# open-ebike-latch.net
KiCad netlist of a schematic drawn in EasyEDA
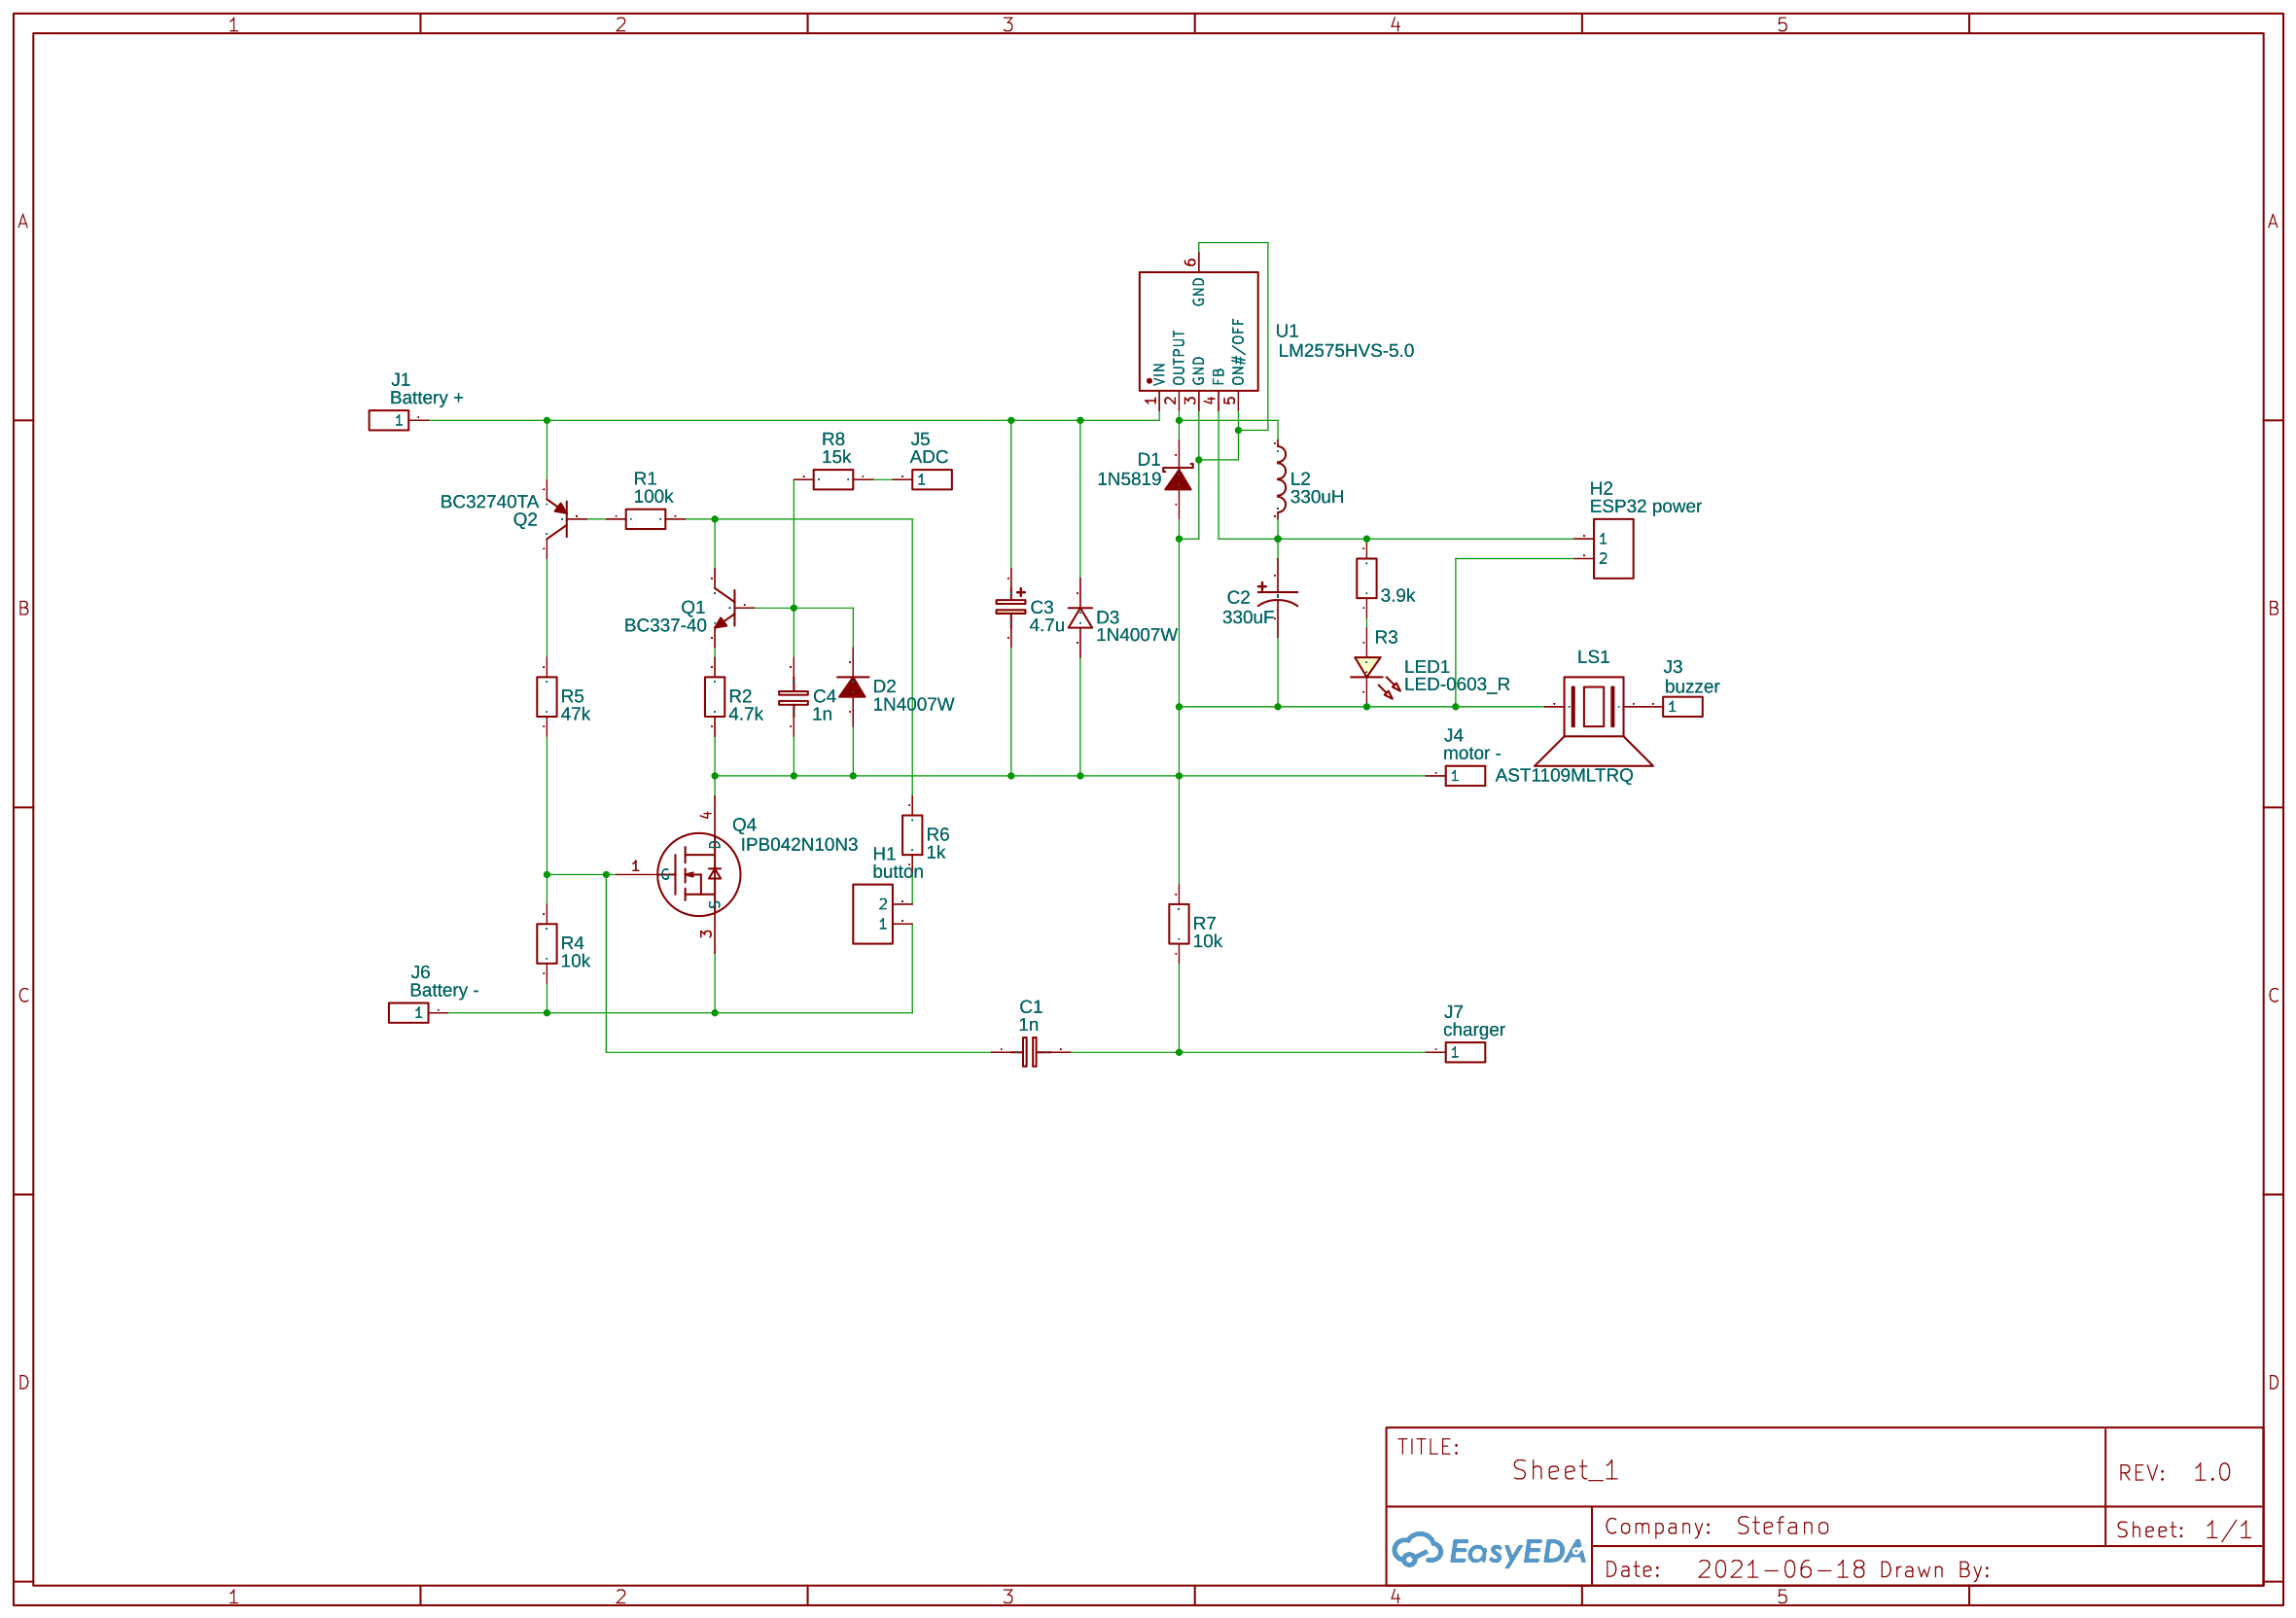
[diagram p0: schematic sheet]

(export (version "E")
  (design (tool "Eeschema 10.0.6"))
  (components
    (comp (ref "C1") (value "1n") (libsource (lib "") (part "C_RAD-0.2_EU_1")))
    (comp (ref "C2")
      (value "330uF")
      (fields
        (field (name "BOM_Manufacturer Part") "UWX0J331MCL1GB")
        (field (name "BOM_Supplier Part") "C445051")
      )
      (libsource (lib "") (part "UWX0J331MCL1GB"))
    )
    (comp (ref "C3") (value "4.7u") (libsource (lib "") (part "CE_TH_D5.0×F2.0_EU")))
    (comp (ref "C4") (value "1n") (libsource (lib "") (part "C_RAD-0.2_EU")))
    (comp (ref "D1")
      (value "1N5819")
      (fields (field (name "BOM_Supplier Part") "C110032"))
      (libsource (lib "") (part "1N5819"))
    )
    (comp (ref "D2")
      (value "1N4007W")
      (fields (field (name "BOM_Supplier Part") "C14516"))
      (libsource (lib "") (part "1N4148"))
    )
    (comp (ref "D3")
      (value "1N4007W")
      (fields (field (name "BOM_Supplier Part") "C328592"))
      (libsource (lib "") (part "1N4007W"))
    )
    (comp (ref "H1")
      (value "button")
      (fields (field (name "BOM_Supplier Part") "C49661"))
      (libsource (lib "") (part "HDR-F-2.54_1x2"))
    )
    (comp (ref "H2")
      (value "ESP32 power")
      (fields (field (name "BOM_Supplier Part") "C49661"))
      (libsource (lib "") (part "HDR-F-2.54_1x2_1"))
    )
    (comp (ref "J1")
      (value "Battery +")
      (fields (field (name "BOM_Supplier Part") "C81276"))
      (libsource (lib "") (part "HDR-M-2.54_1x1_1"))
    )
    (comp (ref "J3")
      (value "buzzer")
      (fields (field (name "BOM_Supplier Part") "C81276"))
      (libsource (lib "") (part "HDR-M-2.54_1x1"))
    )
    (comp (ref "J4")
      (value "motor -")
      (fields (field (name "BOM_Supplier Part") "C81276"))
      (libsource (lib "") (part "HDR-M-2.54_1x1"))
    )
    (comp (ref "J5")
      (value "ADC")
      (fields (field (name "BOM_Supplier Part") "C81276"))
      (libsource (lib "") (part "HDR-M-2.54_1x1"))
    )
    (comp (ref "J6")
      (value "Battery -")
      (fields (field (name "BOM_Supplier Part") "C81276"))
      (libsource (lib "") (part "HDR-M-2.54_1x1_1"))
    )
    (comp (ref "J7")
      (value "charger")
      (fields (field (name "BOM_Supplier Part") "C81276"))
      (libsource (lib "") (part "HDR-M-2.54_1x1"))
    )
    (comp (ref "L2")
      (value "330uH")
      (fields
        (field (name "BOM_Manufacturer Part") "CKL0510*330uH/K-A T")
        (field (name "BOM_Supplier Part") "C354671")
      )
      (libsource (lib "") (part "CKL0510*330UH/K-A T"))
    )
    (comp (ref "LED1")
      (value "LED-0603_R")
      (fields
        (field (name "BOM_Manufacturer Part") "19-217/R6C-AL1M2VY/3T")
        (field (name "BOM_Supplier Part") "C72044")
      )
      (libsource (lib "") (part "LED-0603_R"))
    )
    (comp (ref "LS1")
      (value "AST1109MLTRQ")
      (fields (field (name "BOM_Supplier Part") "458-1093-1-ND"))
      (libsource (lib "") (part "AST1109MLTRQ"))
    )
    (comp (ref "Q1")
      (value "BC337-40")
      (fields (field (name "BOM_Supplier Part") "C713611"))
      (libsource (lib "") (part "BC337-40"))
    )
    (comp (ref "Q2")
      (value "BC32740TA")
      (fields (field (name "BOM_Supplier Part") "C900785"))
      (libsource (lib "") (part "BC32740TA"))
    )
    (comp (ref "Q4")
      (value "IPB042N10N3")
      (fields
        (field (name "BOM_Manufacturer Part") "IRFS4310ZTRLPBF")
        (field (name "BOM_Supplier Part") "C148160")
      )
      (libsource (lib "") (part "IRFS4310ZTRLPBF"))
    )
    (comp (ref "R1") (value "100k") (libsource (lib "") (part "R_AXIAL-0.5_EU_2")))
    (comp (ref "R2") (value "4.7k") (libsource (lib "") (part "R_AXIAL-0.5_EU_1")))
    (comp (ref "R3") (value "3.9k") (libsource (lib "") (part "R_AXIAL-0.5_EU_1")))
    (comp (ref "R4") (value "10k") (libsource (lib "") (part "R_AXIAL-0.5_EU_1")))
    (comp (ref "R5") (value "47k") (libsource (lib "") (part "R_AXIAL-0.5_EU_1")))
    (comp (ref "R6") (value "1k") (libsource (lib "") (part "R_AXIAL-0.5_EU_1")))
    (comp (ref "R7") (value "10k") (libsource (lib "") (part "R_AXIAL-0.5_EU_1")))
    (comp (ref "R8") (value "15k") (libsource (lib "") (part "R_AXIAL-0.5_EU")))
    (comp (ref "U1")
      (value "LM2575HVS-5.0")
      (fields (field (name "BOM_Supplier Part") "C434502"))
      (libsource (lib "") (part "LM2575HVS-5.0"))
    )
  )
  (nets
    (net (code "1") (name "Net-(C1-Pad2)") (class "Default")
      (node (ref "C1") (pin "2") (pinfunction "2_2") (pintype "unspecified"))
      (node (ref "J7") (pin "1") (pinfunction "1_1") (pintype "input"))
      (node (ref "R7") (pin "1") (pinfunction "1_1") (pintype "unspecified"))
    )
    (net (code "2") (name "Net-(D1-A)") (class "Default")
      (node (ref "C2") (pin "2") (pinfunction "2_2") (pintype "unspecified"))
      (node (ref "C3") (pin "2") (pinfunction "2_2") (pintype "unspecified"))
      (node (ref "C4") (pin "1") (pinfunction "1_1") (pintype "unspecified"))
      (node (ref "D1") (pin "1") (pinfunction "A_1") (pintype "unspecified"))
      (node (ref "D2") (pin "1") (pinfunction "A_1") (pintype "unspecified"))
      (node (ref "D3") (pin "2") (pinfunction "2_2") (pintype "unspecified"))
      (node (ref "H2") (pin "2") (pinfunction "2_2") (pintype "input"))
      (node (ref "J4") (pin "1") (pinfunction "1_1") (pintype "input"))
      (node (ref "LED1") (pin "2") (pinfunction "2_2") (pintype "unspecified"))
      (node (ref "LS1") (pin "2") (pinfunction "2_2") (pintype "unspecified"))
      (node (ref "Q4") (pin "4") (pinfunction "D_4") (pintype "unspecified"))
      (node (ref "R2") (pin "1") (pinfunction "1_1") (pintype "unspecified"))
      (node (ref "R7") (pin "2") (pinfunction "2_2") (pintype "unspecified"))
      (node (ref "U1") (pin "3") (pinfunction "GND_3") (pintype "unspecified"))
      (node (ref "U1") (pin "5") (pinfunction "ON#/OFF_5") (pintype "unspecified"))
      (node (ref "U1") (pin "6") (pinfunction "GND_6") (pintype "unspecified"))
    )
    (net (code "3") (name "Net-(D1-K)") (class "Default")
      (node (ref "D1") (pin "2") (pinfunction "K_2") (pintype "unspecified"))
      (node (ref "L2") (pin "1") (pinfunction "1_1") (pintype "unspecified"))
      (node (ref "U1") (pin "2") (pinfunction "OUTPUT_2") (pintype "unspecified"))
    )
    (net (code "4") (name "Net-(D2-C)") (class "Default")
      (node (ref "C4") (pin "2") (pinfunction "2_2") (pintype "unspecified"))
      (node (ref "D2") (pin "2") (pinfunction "C_2") (pintype "unspecified"))
      (node (ref "Q1") (pin "2") (pinfunction "B_2") (pintype "input"))
      (node (ref "R8") (pin "2") (pinfunction "2_2") (pintype "unspecified"))
    )
    (net (code "5") (name "Net-(H1-Pad2)") (class "Default")
      (node (ref "H1") (pin "2") (pinfunction "2_2") (pintype "input"))
      (node (ref "R6") (pin "1") (pinfunction "1_1") (pintype "unspecified"))
    )
    (net (code "6") (name "Net-(J3-Pad1)") (class "Default")
      (node (ref "J3") (pin "1") (pinfunction "1_1") (pintype "input"))
      (node (ref "LS1") (pin "1") (pinfunction "1_1") (pintype "unspecified"))
    )
    (net (code "7") (name "Net-(J5-Pad1)") (class "Default")
      (node (ref "J5") (pin "1") (pinfunction "1_1") (pintype "input"))
      (node (ref "R8") (pin "1") (pinfunction "1_1") (pintype "unspecified"))
    )
    (net (code "8") (name "Net-(LED1-Pad1)") (class "Default")
      (node (ref "LED1") (pin "1") (pinfunction "1_1") (pintype "unspecified"))
      (node (ref "R3") (pin "1") (pinfunction "1_1") (pintype "unspecified"))
    )
    (net (code "9") (name "Net-(Q1-C)") (class "Default")
      (node (ref "Q1") (pin "1") (pinfunction "C_1") (pintype "input"))
      (node (ref "R1") (pin "2") (pinfunction "2_2") (pintype "unspecified"))
      (node (ref "R6") (pin "2") (pinfunction "2_2") (pintype "unspecified"))
    )
    (net (code "10") (name "Net-(Q1-E)") (class "Default")
      (node (ref "Q1") (pin "3") (pinfunction "E_3") (pintype "input"))
      (node (ref "R2") (pin "2") (pinfunction "2_2") (pintype "unspecified"))
    )
    (net (code "11") (name "Net-(Q2-B)") (class "Default")
      (node (ref "Q2") (pin "2") (pinfunction "B_2") (pintype "input"))
      (node (ref "R1") (pin "1") (pinfunction "1_1") (pintype "unspecified"))
    )
    (net (code "12") (name "Net-(Q2-C)") (class "Default")
      (node (ref "Q2") (pin "1") (pinfunction "C_1") (pintype "input"))
      (node (ref "R5") (pin "2") (pinfunction "2_2") (pintype "unspecified"))
    )
    (net (code "13") (name "Net-(Q2-E)") (class "Default")
      (node (ref "C3") (pin "1") (pinfunction "1_1") (pintype "unspecified"))
      (node (ref "D3") (pin "1") (pinfunction "1_1") (pintype "unspecified"))
      (node (ref "J1") (pin "1") (pinfunction "1_1") (pintype "input"))
      (node (ref "Q2") (pin "3") (pinfunction "E_3") (pintype "input"))
      (node (ref "U1") (pin "1") (pinfunction "VIN_1") (pintype "unspecified"))
    )
    (net (code "14") (name "Net-(Q4-G)") (class "Default")
      (node (ref "C1") (pin "1") (pinfunction "1_1") (pintype "unspecified"))
      (node (ref "Q4") (pin "1") (pinfunction "G_1") (pintype "unspecified"))
      (node (ref "R4") (pin "2") (pinfunction "2_2") (pintype "unspecified"))
      (node (ref "R5") (pin "1") (pinfunction "1_1") (pintype "unspecified"))
    )
    (net (code "15") (name "Net-(Q4-S)") (class "Default")
      (node (ref "H1") (pin "1") (pinfunction "1_1") (pintype "input"))
      (node (ref "J6") (pin "1") (pinfunction "1_1") (pintype "input"))
      (node (ref "Q4") (pin "3") (pinfunction "S_3") (pintype "unspecified"))
      (node (ref "R4") (pin "1") (pinfunction "1_1") (pintype "unspecified"))
    )
    (net (code "16") (name "Net-(U1-FB)") (class "Default")
      (node (ref "C2") (pin "1") (pinfunction "1_1") (pintype "unspecified"))
      (node (ref "H2") (pin "1") (pinfunction "1_1") (pintype "input"))
      (node (ref "L2") (pin "2") (pinfunction "2_2") (pintype "unspecified"))
      (node (ref "R3") (pin "2") (pinfunction "2_2") (pintype "unspecified"))
      (node (ref "U1") (pin "4") (pinfunction "FB_4") (pintype "unspecified"))
    )
  )
)
